# DE-180417_01.net
KiCad netlist of a schematic drawn in Altium Designer
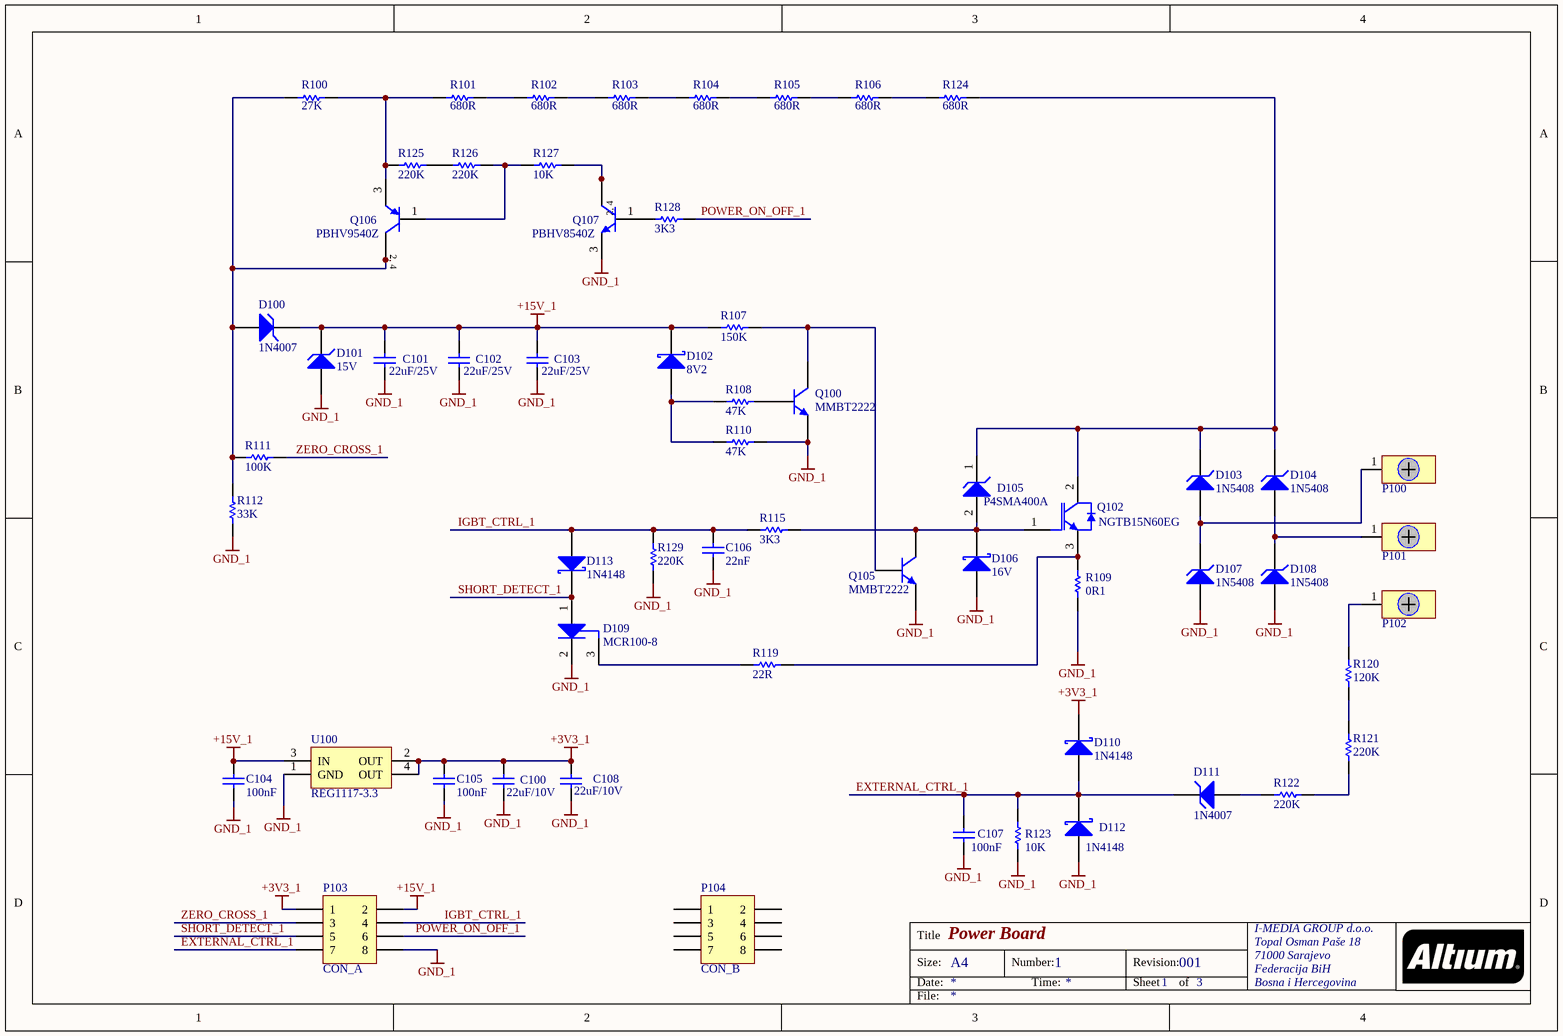
[diagram p0: DE-180417_01.SchDoc]

(export (version "E")
  (design (tool "Eeschema 10.0.6"))
  (components
    (comp (ref "C100")
      (value "22uF/10V")
      (footprint "1210")
      (description "Ceramic Chip Capacitor - Standard")
      (fields (field (name "PUBLISHER") "Altium Limited"))
      (libsource (lib "KEMET Chip Capacitor") (part "C1210"))
    )
    (comp (ref "C101")
      (value "22uF/25V")
      (footprint "1210")
      (description "Ceramic Chip Capacitor - Standard")
      (fields (field (name "PUBLISHER") "Altium Limited"))
      (libsource (lib "KEMET Chip Capacitor") (part "C1210"))
    )
    (comp (ref "C102")
      (value "22uF/25V")
      (footprint "1210")
      (description "Ceramic Chip Capacitor - Standard")
      (fields (field (name "PUBLISHER") "Altium Limited"))
      (libsource (lib "KEMET Chip Capacitor") (part "C1210"))
    )
    (comp (ref "C103")
      (value "22uF/25V")
      (footprint "1210")
      (description "Ceramic Chip Capacitor - Standard")
      (fields (field (name "PUBLISHER") "Altium Limited"))
      (libsource (lib "KEMET Chip Capacitor") (part "C1210"))
    )
    (comp (ref "C104")
      (value "100nF")
      (footprint "0603")
      (description "Ceramic Chip Capacitor - Standard")
      (fields (field (name "PUBLISHER") "Altium Limited"))
      (libsource (lib "DE-180417") (part "C0603"))
    )
    (comp (ref "C105")
      (value "100nF")
      (footprint "0603")
      (description "Ceramic Chip Capacitor - Standard")
      (fields (field (name "PUBLISHER") "Altium Limited"))
      (libsource (lib "DE-180417") (part "C0603"))
    )
    (comp (ref "C106")
      (value "22nF")
      (footprint "0603")
      (description "Ceramic Chip Capacitor - Standard")
      (fields (field (name "PUBLISHER") "Altium Limited"))
      (libsource (lib "DE-180417") (part "C0603"))
    )
    (comp (ref "C107")
      (value "100nF")
      (footprint "0603")
      (description "Ceramic Chip Capacitor - Standard")
      (fields (field (name "PUBLISHER") "Altium Limited"))
      (libsource (lib "DE-180417") (part "C0603"))
    )
    (comp (ref "C108")
      (value "22uF/10V")
      (footprint "1210")
      (description "Ceramic Chip Capacitor - Standard")
      (fields (field (name "PUBLISHER") "Altium Limited"))
      (libsource (lib "KEMET Chip Capacitor") (part "C1210"))
    )
    (comp (ref "D100")
      (value "1N4007")
      (footprint "DO214")
      (description "Silicon Zener Diode (3W)")
      (fields (field (name "PUBLISHER") "Altium Limited"))
      (libsource (lib "Vishay Telefunken Discrete Diode") (part "BZG03C10"))
    )
    (comp (ref "D101")
      (value "15V")
      (footprint "DO214")
      (description "Silicon Zener Diode (3W)")
      (fields (field (name "PUBLISHER") "Altium Limited"))
      (libsource (lib "Vishay Telefunken Discrete Diode") (part "BZG05C15"))
    )
    (comp (ref "D102")
      (value "8V2")
      (footprint "SOD323")
      (description "Schottky Barrier Diode")
      (fields (field (name "PUBLISHER") "Altium Limited"))
      (libsource (lib "Philips Discrete Diode - Schottky") (part "1PS76SB10"))
    )
    (comp (ref "D103")
      (value "1N5408")
      (footprint "DO214")
      (description "Silicon Zener Diode (3W)")
      (fields (field (name "PUBLISHER") "Altium Limited"))
      (libsource (lib "Vishay Telefunken Discrete Diode") (part "BZG05C15"))
    )
    (comp (ref "D104")
      (value "1N5408")
      (footprint "DO214")
      (description "Silicon Zener Diode (3W)")
      (fields (field (name "PUBLISHER") "Altium Limited"))
      (libsource (lib "Vishay Telefunken Discrete Diode") (part "BZG05C15"))
    )
    (comp (ref "D105")
      (value "P4SMA400A")
      (footprint "ONSC-SMC-2-403-03_V")
      (fields (field (name "MANUFACTURER") "On Semiconductor") (field (name "PARTNUMBER") "1SMC9.0AT3G"))
      (libsource (lib "ON Semi Transient Voltage Suppressors (TVS)") (part "1SMC9.0AT3G"))
    )
    (comp (ref "D106")
      (value "16V")
      (footprint "SOD323")
      (description "Schottky Barrier Diode")
      (fields (field (name "PUBLISHER") "Altium Limited"))
      (libsource (lib "Philips Discrete Diode - Schottky") (part "1PS76SB10"))
    )
    (comp (ref "D107")
      (value "1N5408")
      (footprint "DO214")
      (description "Silicon Zener Diode (3W)")
      (fields (field (name "PUBLISHER") "Altium Limited"))
      (libsource (lib "Vishay Telefunken Discrete Diode") (part "BZG05C15"))
    )
    (comp (ref "D108")
      (value "1N5408")
      (footprint "DO214")
      (description "Silicon Zener Diode (3W)")
      (fields (field (name "PUBLISHER") "Altium Limited"))
      (libsource (lib "Vishay Telefunken Discrete Diode") (part "BZG05C15"))
    )
    (comp (ref "D109")
      (value "MCR100-8")
      (footprint "INF-SOT89_N")
      (description "Silicon Switching Diode, SOT89, Reel, Green")
      (fields (field (name "MANUFACTURER") "Infineon") (field (name "PARTNUMBER") "BAW78D"))
      (libsource (lib "Infineon_Transistor_&_Diode") (part "BAW78D"))
    )
    (comp (ref "D110")
      (value "1N4148")
      (footprint "SOD323")
      (description "Schottky Barrier Diode")
      (fields (field (name "PUBLISHER") "Altium Limited"))
      (libsource (lib "Philips Discrete Diode - Schottky") (part "1PS76SB10"))
    )
    (comp (ref "D111")
      (value "1N4007")
      (footprint "DO214")
      (description "Silicon Zener Diode (3W)")
      (fields (field (name "PUBLISHER") "Altium Limited"))
      (libsource (lib "Vishay Telefunken Discrete Diode") (part "BZG03C10"))
    )
    (comp (ref "D112")
      (value "1N4148")
      (footprint "SOD323")
      (description "Schottky Barrier Diode")
      (fields (field (name "PUBLISHER") "Altium Limited"))
      (libsource (lib "Philips Discrete Diode - Schottky") (part "1PS76SB10"))
    )
    (comp (ref "D113")
      (value "1N4148")
      (footprint "SOD323")
      (description "Schottky Barrier Diode")
      (fields (field (name "PUBLISHER") "Altium Limited"))
      (libsource (lib "Philips Discrete Diode - Schottky") (part "1PS76SB10"))
    )
    (comp (ref "P100")
      (value "Single Wire Lug")
      (footprint "Single Wire Lug")
      (libsource (lib "DE-180417") (part "Wire Lug"))
    )
    (comp (ref "P101")
      (value "Single Wire Lug")
      (footprint "Single Wire Lug")
      (libsource (lib "DE-180417") (part "Wire Lug"))
    )
    (comp (ref "P102")
      (value "Single Wire Lug")
      (footprint "Single Wire Lug")
      (libsource (lib "DE-180417") (part "Wire Lug"))
    )
    (comp (ref "P103")
      (value "CON_A")
      (footprint "HDR2X4")
      (description "Header, 4-Pin, Dual row")
      (fields (field (name "PUBLISHER") "Altium Limited"))
      (libsource (lib "Miscellaneous Connectors") (part "Header 4X2"))
    )
    (comp (ref "P104")
      (value "CON_B")
      (footprint "HDR2X4")
      (description "Header, 4-Pin, Dual row")
      (fields (field (name "PUBLISHER") "Altium Limited"))
      (libsource (lib "Miscellaneous Connectors") (part "Header 4X2"))
    )
    (comp (ref "Q100")
      (value "MMBT2222")
      (footprint "SOT23_N")
      (description "NPN General-purpose Transistor")
      (fields (field (name "PUBLISHER") "Altium Limited"))
      (libsource (lib "DE-180417") (part "BC817"))
    )
    (comp (ref "Q102")
      (value "NGTB15N60EG")
      (footprint "ONSC-TO-220-3-221A-09")
      (description "IGBT - Short-Circuit Rated, 3-Pin TO-220, Pb-Free, Tube")
      (fields (field (name "MANUFACTURER") "On Semiconductor"))
      (libsource (lib "ON Semi IGBTs") (part "NGTB15N60EG"))
    )
    (comp (ref "Q105")
      (value "MMBT2222")
      (footprint "SOT23_N")
      (description "NPN General-purpose Transistor")
      (fields (field (name "PUBLISHER") "Altium Limited"))
      (libsource (lib "DE-180417") (part "BC817"))
    )
    (comp (ref "Q106")
      (value "PBHV9540Z")
      (footprint "SOT223_N")
      (description "PNP Medium Power Transistor")
      (fields (field (name "PUBLISHER") "Altium Limited"))
      (libsource (lib "Philips Discrete BJT - Medium Power") (part "BCP51"))
    )
    (comp (ref "Q107")
      (value "PBHV8540Z")
      (footprint "SOT223_N")
      (description "NPN Medium Power Transistor")
      (fields (field (name "PUBLISHER") "Altium Limited"))
      (libsource (lib "Philips Discrete BJT - Medium Power") (part "BCP54"))
    )
    (comp (ref "R100")
      (value "27K")
      (footprint "12-1812")
      (description "Thick Film Chip Resistor, 1 Ohm to 10M Ohm Range, 5% Tolerance, 1812 Size, 0.5 W")
      (fields (field (name "PUBLISHER") "Altium Limited"))
      (libsource (lib "Panasonic Resistor") (part "ERJ12"))
    )
    (comp (ref "R101")
      (value "680R")
      (footprint "12-1812")
      (description "Thick Film Chip Resistor, 1 Ohm to 10M Ohm Range, 5% Tolerance, 1812 Size, 0.5 W")
      (fields (field (name "PUBLISHER") "Altium Limited"))
      (libsource (lib "Panasonic Resistor") (part "ERJ12"))
    )
    (comp (ref "R102")
      (value "680R")
      (footprint "12-1812")
      (description "Thick Film Chip Resistor, 1 Ohm to 10M Ohm Range, 5% Tolerance, 1812 Size, 0.5 W")
      (fields (field (name "PUBLISHER") "Altium Limited"))
      (libsource (lib "Panasonic Resistor") (part "ERJ12"))
    )
    (comp (ref "R103")
      (value "680R")
      (footprint "12-1812")
      (description "Thick Film Chip Resistor, 1 Ohm to 10M Ohm Range, 5% Tolerance, 1812 Size, 0.5 W")
      (fields (field (name "PUBLISHER") "Altium Limited"))
      (libsource (lib "Panasonic Resistor") (part "ERJ12"))
    )
    (comp (ref "R104")
      (value "680R")
      (footprint "12-1812")
      (description "Thick Film Chip Resistor, 1 Ohm to 10M Ohm Range, 5% Tolerance, 1812 Size, 0.5 W")
      (fields (field (name "PUBLISHER") "Altium Limited"))
      (libsource (lib "Panasonic Resistor") (part "ERJ12"))
    )
    (comp (ref "R105")
      (value "680R")
      (footprint "12-1812")
      (description "Thick Film Chip Resistor, 1 Ohm to 10M Ohm Range, 5% Tolerance, 1812 Size, 0.5 W")
      (fields (field (name "PUBLISHER") "Altium Limited"))
      (libsource (lib "Panasonic Resistor") (part "ERJ12"))
    )
    (comp (ref "R106")
      (value "680R")
      (footprint "12-1812")
      (description "Thick Film Chip Resistor, 1 Ohm to 10M Ohm Range, 5% Tolerance, 1812 Size, 0.5 W")
      (fields (field (name "PUBLISHER") "Altium Limited"))
      (libsource (lib "Panasonic Resistor") (part "ERJ12"))
    )
    (comp (ref "R107")
      (value "150K")
      (footprint "ERA-0603")
      (fields (field (name "PUBLISHER") "Altium Limited"))
      (libsource (lib "DE-180417") (part "ERAV"))
    )
    (comp (ref "R108")
      (value "47K")
      (footprint "ERA-0603")
      (fields (field (name "PUBLISHER") "Altium Limited"))
      (libsource (lib "DE-180417") (part "ERAV"))
    )
    (comp (ref "R109")
      (value "0R1")
      (footprint "14-1210")
      (description "Thick Film Chip Resistor, 1 Ohm to 10M Ohm Range, 5% Tolerance, 1210 Size, 0.25 W")
      (fields (field (name "PUBLISHER") "Altium Limited"))
      (libsource (lib "Panasonic Resistor") (part "ERJ14"))
    )
    (comp (ref "R110")
      (value "47K")
      (footprint "ERA-0603")
      (fields (field (name "PUBLISHER") "Altium Limited"))
      (libsource (lib "DE-180417") (part "ERAV"))
    )
    (comp (ref "R111")
      (value "100K")
      (footprint "ERA-0603")
      (fields (field (name "PUBLISHER") "Altium Limited"))
      (libsource (lib "DE-180417") (part "ERAV"))
    )
    (comp (ref "R112")
      (value "33K")
      (footprint "ERA-0805")
      (fields (field (name "PUBLISHER") "Altium Limited"))
      (libsource (lib "Panasonic Resistor") (part "ERA6Y"))
    )
    (comp (ref "R115")
      (value "3K3")
      (footprint "ERA-0603")
      (fields (field (name "PUBLISHER") "Altium Limited"))
      (libsource (lib "DE-180417") (part "ERAV"))
    )
    (comp (ref "R119")
      (value "22R")
      (footprint "ERA-0603")
      (fields (field (name "PUBLISHER") "Altium Limited"))
      (libsource (lib "DE-180417") (part "ERAV"))
    )
    (comp (ref "R120")
      (value "120K")
      (footprint "ERA-0805")
      (fields (field (name "PUBLISHER") "Altium Limited"))
      (libsource (lib "Panasonic Resistor") (part "ERA6Y"))
    )
    (comp (ref "R121")
      (value "220K")
      (footprint "ERA-0805")
      (fields (field (name "PUBLISHER") "Altium Limited"))
      (libsource (lib "Panasonic Resistor") (part "ERA6Y"))
    )
    (comp (ref "R122")
      (value "220K")
      (footprint "ERA-0805")
      (fields (field (name "PUBLISHER") "Altium Limited"))
      (libsource (lib "Panasonic Resistor") (part "ERA6Y"))
    )
    (comp (ref "R123")
      (value "10K")
      (footprint "ERA-0603")
      (fields (field (name "PUBLISHER") "Altium Limited"))
      (libsource (lib "DE-180417") (part "ERAV"))
    )
    (comp (ref "R124")
      (value "680R")
      (footprint "12-1812")
      (description "Thick Film Chip Resistor, 1 Ohm to 10M Ohm Range, 5% Tolerance, 1812 Size, 0.5 W")
      (fields (field (name "PUBLISHER") "Altium Limited"))
      (libsource (lib "Panasonic Resistor") (part "ERJ12"))
    )
    (comp (ref "R125")
      (value "220K")
      (footprint "ERA-0805")
      (fields (field (name "PUBLISHER") "Altium Limited"))
      (libsource (lib "DE-180417") (part "ERA6Y"))
    )
    (comp (ref "R126")
      (value "220K")
      (footprint "ERA-0805")
      (fields (field (name "PUBLISHER") "Altium Limited"))
      (libsource (lib "DE-180417") (part "ERA6Y"))
    )
    (comp (ref "R127")
      (value "10K")
      (footprint "ERA-0805")
      (fields (field (name "PUBLISHER") "Altium Limited"))
      (libsource (lib "DE-180417") (part "ERA6Y"))
    )
    (comp (ref "R128")
      (value "3K3")
      (footprint "ERA-0805")
      (fields (field (name "PUBLISHER") "Altium Limited"))
      (libsource (lib "DE-180417") (part "ERA6Y"))
    )
    (comp (ref "R129")
      (value "220K")
      (footprint "ERA-0603")
      (fields (field (name "PUBLISHER") "Altium Limited"))
      (libsource (lib "DE-180417") (part "ERAV"))
    )
    (comp (ref "U100")
      (value "REG1117-3.3")
      (footprint "ZZ311")
      (description "800mA and 1A Low Dropout Positive Regulator 2.85V, 3.3V, 5V, and Adjustable")
      (fields (field (name "PUBLISHER") "Altium Limited"))
      (libsource (lib "DE-180417") (part "REG1117-3.3"))
    )
  )
  (nets
    (net (code "1") (name "+3V3_1") (class "Default")
      (node (ref "C100") (pin "2") (pinfunction "2_2") (pintype "passive"))
      (node (ref "C105") (pin "2") (pinfunction "2_2") (pintype "passive"))
      (node (ref "C108") (pin "2") (pinfunction "2_2") (pintype "passive"))
      (node (ref "D110") (pin "1") (pinfunction "K_1") (pintype "passive"))
      (node (ref "P103") (pin "1") (pinfunction "1_1") (pintype "passive"))
      (node (ref "U100") (pin "2") (pinfunction "OUT_2") (pintype "power_in"))
      (node (ref "U100") (pin "4") (pinfunction "OUT_4") (pintype "power_in"))
    )
    (net (code "2") (name "+15V_1") (class "Default")
      (node (ref "C101") (pin "2") (pinfunction "2_2") (pintype "passive"))
      (node (ref "C102") (pin "2") (pinfunction "2_2") (pintype "passive"))
      (node (ref "C103") (pin "2") (pinfunction "2_2") (pintype "passive"))
      (node (ref "C104") (pin "2") (pinfunction "2_2") (pintype "passive"))
      (node (ref "D100") (pin "2") (pinfunction "K_2") (pintype "passive"))
      (node (ref "D101") (pin "2") (pinfunction "K_2") (pintype "passive"))
      (node (ref "D102") (pin "1") (pinfunction "K_1") (pintype "passive"))
      (node (ref "P103") (pin "2") (pinfunction "2_2") (pintype "passive"))
      (node (ref "R107") (pin "1") (pinfunction "1_1") (pintype "passive"))
      (node (ref "U100") (pin "3") (pinfunction "IN_3") (pintype "power_in"))
    )
    (net (code "3") (name "/EXTERNAL_CTRL_1") (class "Default")
      (node (ref "C107") (pin "2") (pinfunction "2_2") (pintype "passive"))
      (node (ref "D110") (pin "2") (pinfunction "A_2") (pintype "passive"))
      (node (ref "D111") (pin "2") (pinfunction "K_2") (pintype "passive"))
      (node (ref "D112") (pin "1") (pinfunction "K_1") (pintype "passive"))
      (node (ref "P103") (pin "7") (pinfunction "7_7") (pintype "passive"))
      (node (ref "R123") (pin "2") (pinfunction "2_2") (pintype "passive"))
    )
    (net (code "4") (name "/IGBT_CTRL_1") (class "Default")
      (node (ref "C106") (pin "2") (pinfunction "2_2") (pintype "passive"))
      (node (ref "D113") (pin "2") (pinfunction "A_2") (pintype "passive"))
      (node (ref "P103") (pin "4") (pinfunction "4_4") (pintype "passive"))
      (node (ref "R115") (pin "1") (pinfunction "1_1") (pintype "passive"))
      (node (ref "R129") (pin "2") (pinfunction "2_2") (pintype "passive"))
    )
    (net (code "5") (name "/POWER_ON_OFF_1") (class "Default")
      (node (ref "P103") (pin "6") (pinfunction "6_6") (pintype "passive"))
      (node (ref "R128") (pin "1") (pinfunction "1_1") (pintype "passive"))
    )
    (net (code "6") (name "/SHORT_DETECT_1") (class "Default")
      (node (ref "D109") (pin "1") (pinfunction "A_1") (pintype "passive"))
      (node (ref "D113") (pin "1") (pinfunction "K_1") (pintype "passive"))
      (node (ref "P103") (pin "5") (pinfunction "5_5") (pintype "passive"))
    )
    (net (code "7") (name "/ZERO_CROSS_1") (class "Default")
      (node (ref "P103") (pin "3") (pinfunction "3_3") (pintype "passive"))
      (node (ref "R111") (pin "1") (pinfunction "1_1") (pintype "passive"))
    )
    (net (code "8") (name "GND_1") (class "Default")
      (node (ref "C100") (pin "1") (pinfunction "1_1") (pintype "passive"))
      (node (ref "C101") (pin "1") (pinfunction "1_1") (pintype "passive"))
      (node (ref "C102") (pin "1") (pinfunction "1_1") (pintype "passive"))
      (node (ref "C103") (pin "1") (pinfunction "1_1") (pintype "passive"))
      (node (ref "C104") (pin "1") (pinfunction "1_1") (pintype "passive"))
      (node (ref "C105") (pin "1") (pinfunction "1_1") (pintype "passive"))
      (node (ref "C106") (pin "1") (pinfunction "1_1") (pintype "passive"))
      (node (ref "C107") (pin "1") (pinfunction "1_1") (pintype "passive"))
      (node (ref "C108") (pin "1") (pinfunction "1_1") (pintype "passive"))
      (node (ref "D101") (pin "1") (pinfunction "A_1") (pintype "passive"))
      (node (ref "D106") (pin "2") (pinfunction "A_2") (pintype "passive"))
      (node (ref "D107") (pin "1") (pinfunction "A_1") (pintype "passive"))
      (node (ref "D108") (pin "1") (pinfunction "A_1") (pintype "passive"))
      (node (ref "D109") (pin "2") (pinfunction "K_2") (pintype "passive"))
      (node (ref "D112") (pin "2") (pinfunction "A_2") (pintype "passive"))
      (node (ref "P103") (pin "8") (pinfunction "8_8") (pintype "passive"))
      (node (ref "Q100") (pin "2") (pinfunction "E_2") (pintype "passive"))
      (node (ref "Q105") (pin "2") (pinfunction "E_2") (pintype "passive"))
      (node (ref "Q107") (pin "3") (pinfunction "E_3") (pintype "passive"))
      (node (ref "R109") (pin "1") (pinfunction "1_1") (pintype "passive"))
      (node (ref "R110") (pin "2") (pinfunction "2_2") (pintype "passive"))
      (node (ref "R112") (pin "1") (pinfunction "1_1") (pintype "passive"))
      (node (ref "R123") (pin "1") (pinfunction "1_1") (pintype "passive"))
      (node (ref "R129") (pin "1") (pinfunction "1_1") (pintype "passive"))
      (node (ref "U100") (pin "1") (pinfunction "GND_1") (pintype "power_in"))
    )
    (net (code "9") (name "Net-(D100-A)") (class "Default")
      (node (ref "D100") (pin "1") (pinfunction "A_1") (pintype "passive"))
      (node (ref "Q106") (pin "2") (pinfunction "C_2") (pintype "passive"))
      (node (ref "Q106") (pin "4") (pinfunction "C_4") (pintype "passive"))
      (node (ref "R100") (pin "1") (pinfunction "1_1") (pintype "passive"))
      (node (ref "R111") (pin "2") (pinfunction "2_2") (pintype "passive"))
      (node (ref "R112") (pin "2") (pinfunction "2_2") (pintype "passive"))
    )
    (net (code "10") (name "Net-(D102-A)") (class "Default")
      (node (ref "D102") (pin "2") (pinfunction "A_2") (pintype "passive"))
      (node (ref "R108") (pin "1") (pinfunction "1_1") (pintype "passive"))
      (node (ref "R110") (pin "1") (pinfunction "1_1") (pintype "passive"))
    )
    (net (code "11") (name "Net-(D103-A)") (class "Default")
      (node (ref "D103") (pin "1") (pinfunction "A_1") (pintype "passive"))
      (node (ref "D107") (pin "2") (pinfunction "K_2") (pintype "passive"))
      (node (ref "P100") (pin "1") (pinfunction "1_1") (pintype "passive"))
    )
    (net (code "12") (name "Net-(D103-K)") (class "Default")
      (node (ref "D103") (pin "2") (pinfunction "K_2") (pintype "passive"))
      (node (ref "D104") (pin "2") (pinfunction "K_2") (pintype "passive"))
      (node (ref "D105") (pin "1") (pinfunction "K_1") (pintype "passive"))
      (node (ref "Q102") (pin "2") (pinfunction "C_2") (pintype "passive"))
      (node (ref "R124") (pin "2") (pinfunction "2_2") (pintype "passive"))
    )
    (net (code "13") (name "Net-(D104-A)") (class "Default")
      (node (ref "D104") (pin "1") (pinfunction "A_1") (pintype "passive"))
      (node (ref "D108") (pin "2") (pinfunction "K_2") (pintype "passive"))
      (node (ref "P101") (pin "1") (pinfunction "1_1") (pintype "passive"))
    )
    (net (code "14") (name "Net-(D105-A)") (class "Default")
      (node (ref "D105") (pin "2") (pinfunction "A_2") (pintype "passive"))
      (node (ref "D106") (pin "1") (pinfunction "K_1") (pintype "passive"))
      (node (ref "Q102") (pin "1") (pinfunction "G_1") (pintype "passive"))
      (node (ref "Q105") (pin "3") (pinfunction "C_3") (pintype "passive"))
      (node (ref "R115") (pin "2") (pinfunction "2_2") (pintype "passive"))
    )
    (net (code "15") (name "Net-(D109-G)") (class "Default")
      (node (ref "D109") (pin "3") (pinfunction "G_3") (pintype "passive"))
      (node (ref "R119") (pin "1") (pinfunction "1_1") (pintype "passive"))
    )
    (net (code "16") (name "Net-(D111-A)") (class "Default")
      (node (ref "D111") (pin "1") (pinfunction "A_1") (pintype "passive"))
      (node (ref "R122") (pin "2") (pinfunction "2_2") (pintype "passive"))
    )
    (net (code "17") (name "Net-(P102-Pad1)") (class "Default")
      (node (ref "P102") (pin "1") (pinfunction "1_1") (pintype "passive"))
      (node (ref "R120") (pin "1") (pinfunction "1_1") (pintype "passive"))
    )
    (net (code "18") (name "Net-(Q100-B)") (class "Default")
      (node (ref "Q100") (pin "1") (pinfunction "B_1") (pintype "passive"))
      (node (ref "R108") (pin "2") (pinfunction "2_2") (pintype "passive"))
    )
    (net (code "19") (name "Net-(Q100-C)") (class "Default")
      (node (ref "Q100") (pin "3") (pinfunction "C_3") (pintype "passive"))
      (node (ref "Q105") (pin "1") (pinfunction "B_1") (pintype "passive"))
      (node (ref "R107") (pin "2") (pinfunction "2_2") (pintype "passive"))
    )
    (net (code "20") (name "Net-(Q102-E)") (class "Default")
      (node (ref "Q102") (pin "3") (pinfunction "E_3") (pintype "passive"))
      (node (ref "R109") (pin "2") (pinfunction "2_2") (pintype "passive"))
      (node (ref "R119") (pin "2") (pinfunction "2_2") (pintype "passive"))
    )
    (net (code "21") (name "Net-(Q106-B)") (class "Default")
      (node (ref "Q106") (pin "1") (pinfunction "B_1") (pintype "passive"))
      (node (ref "R126") (pin "1") (pinfunction "1_1") (pintype "passive"))
      (node (ref "R127") (pin "2") (pinfunction "2_2") (pintype "passive"))
    )
    (net (code "22") (name "Net-(Q106-E)") (class "Default")
      (node (ref "Q106") (pin "3") (pinfunction "E_3") (pintype "passive"))
      (node (ref "R100") (pin "2") (pinfunction "2_2") (pintype "passive"))
      (node (ref "R101") (pin "1") (pinfunction "1_1") (pintype "passive"))
      (node (ref "R125") (pin "1") (pinfunction "1_1") (pintype "passive"))
    )
    (net (code "23") (name "Net-(Q107-B)") (class "Default")
      (node (ref "Q107") (pin "1") (pinfunction "B_1") (pintype "passive"))
      (node (ref "R128") (pin "2") (pinfunction "2_2") (pintype "passive"))
    )
    (net (code "24") (name "Net-(Q107-C-Pad2)") (class "Default")
      (node (ref "Q107") (pin "2") (pinfunction "C_2") (pintype "passive"))
      (node (ref "Q107") (pin "4") (pinfunction "C_4") (pintype "passive"))
      (node (ref "R127") (pin "1") (pinfunction "1_1") (pintype "passive"))
    )
    (net (code "25") (name "Net-(R101-Pad2)") (class "Default")
      (node (ref "R101") (pin "2") (pinfunction "2_2") (pintype "passive"))
      (node (ref "R102") (pin "1") (pinfunction "1_1") (pintype "passive"))
    )
    (net (code "26") (name "Net-(R102-Pad2)") (class "Default")
      (node (ref "R102") (pin "2") (pinfunction "2_2") (pintype "passive"))
      (node (ref "R103") (pin "1") (pinfunction "1_1") (pintype "passive"))
    )
    (net (code "27") (name "Net-(R103-Pad2)") (class "Default")
      (node (ref "R103") (pin "2") (pinfunction "2_2") (pintype "passive"))
      (node (ref "R104") (pin "1") (pinfunction "1_1") (pintype "passive"))
    )
    (net (code "28") (name "Net-(R104-Pad2)") (class "Default")
      (node (ref "R104") (pin "2") (pinfunction "2_2") (pintype "passive"))
      (node (ref "R105") (pin "1") (pinfunction "1_1") (pintype "passive"))
    )
    (net (code "29") (name "Net-(R105-Pad2)") (class "Default")
      (node (ref "R105") (pin "2") (pinfunction "2_2") (pintype "passive"))
      (node (ref "R106") (pin "1") (pinfunction "1_1") (pintype "passive"))
    )
    (net (code "30") (name "Net-(R106-Pad2)") (class "Default")
      (node (ref "R106") (pin "2") (pinfunction "2_2") (pintype "passive"))
      (node (ref "R124") (pin "1") (pinfunction "1_1") (pintype "passive"))
    )
    (net (code "31") (name "Net-(R120-Pad2)") (class "Default")
      (node (ref "R120") (pin "2") (pinfunction "2_2") (pintype "passive"))
      (node (ref "R121") (pin "1") (pinfunction "1_1") (pintype "passive"))
    )
    (net (code "32") (name "Net-(R121-Pad2)") (class "Default")
      (node (ref "R121") (pin "2") (pinfunction "2_2") (pintype "passive"))
      (node (ref "R122") (pin "1") (pinfunction "1_1") (pintype "passive"))
    )
    (net (code "33") (name "Net-(R125-Pad2)") (class "Default")
      (node (ref "R125") (pin "2") (pinfunction "2_2") (pintype "passive"))
      (node (ref "R126") (pin "2") (pinfunction "2_2") (pintype "passive"))
    )
    (net (code "34") (name "unconnected-(P104-Pad1)") (class "Default")
      (node (ref "P104") (pin "1") (pinfunction "1_1") (pintype "passive"))
    )
    (net (code "35") (name "unconnected-(P104-Pad2)") (class "Default")
      (node (ref "P104") (pin "2") (pinfunction "2_2") (pintype "passive"))
    )
    (net (code "36") (name "unconnected-(P104-Pad3)") (class "Default")
      (node (ref "P104") (pin "3") (pinfunction "3_3") (pintype "passive"))
    )
    (net (code "37") (name "unconnected-(P104-Pad4)") (class "Default")
      (node (ref "P104") (pin "4") (pinfunction "4_4") (pintype "passive"))
    )
    (net (code "38") (name "unconnected-(P104-Pad5)") (class "Default")
      (node (ref "P104") (pin "5") (pinfunction "5_5") (pintype "passive"))
    )
    (net (code "39") (name "unconnected-(P104-Pad6)") (class "Default")
      (node (ref "P104") (pin "6") (pinfunction "6_6") (pintype "passive"))
    )
    (net (code "40") (name "unconnected-(P104-Pad7)") (class "Default")
      (node (ref "P104") (pin "7") (pinfunction "7_7") (pintype "passive"))
    )
    (net (code "41") (name "unconnected-(P104-Pad8)") (class "Default")
      (node (ref "P104") (pin "8") (pinfunction "8_8") (pintype "passive"))
    )
  )
)
